# SCH_pump_2021-09-05_easyeda.net
KiCad netlist of a schematic drawn in EasyEDA
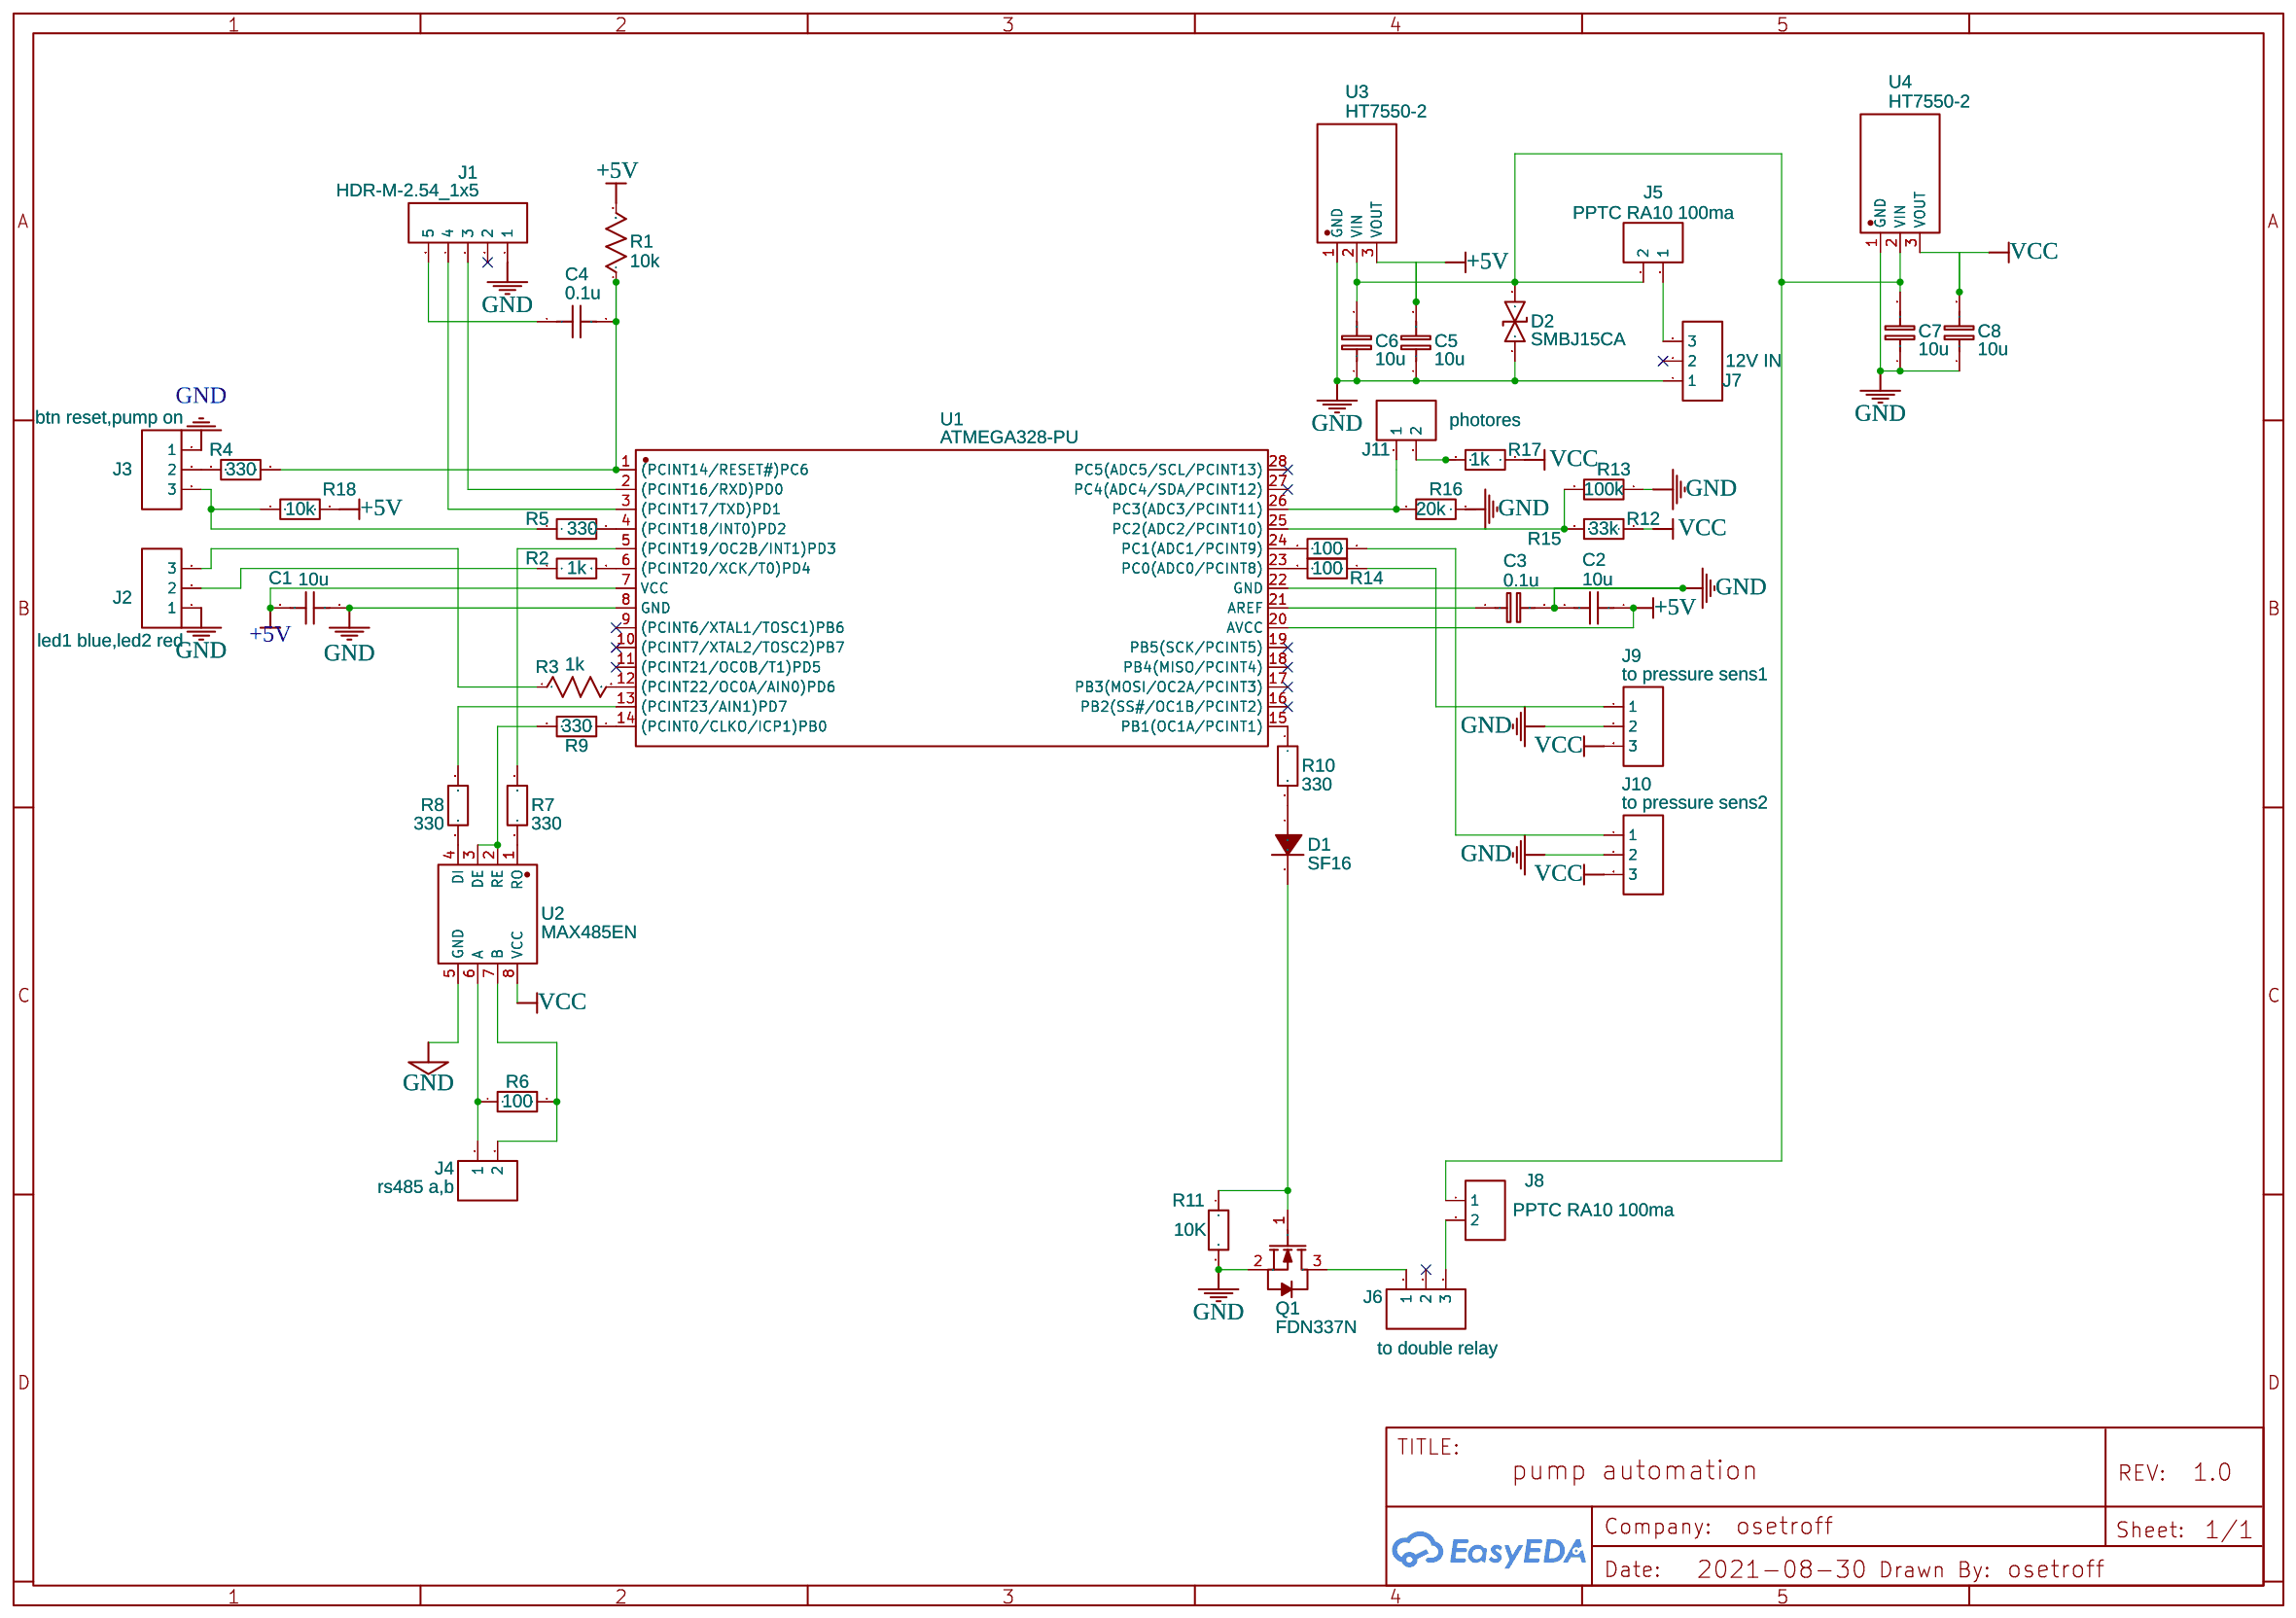
[diagram p0: schematic sheet]

(export (version "E")
  (design (tool "Eeschema 10.0.6"))
  (components
    (comp (ref "C1") (value "10u") (libsource (lib "") (part "C_0603_US")))
    (comp (ref "C2") (value "10u") (libsource (lib "") (part "C_0603_US")))
    (comp (ref "C3") (value "0.1u") (libsource (lib "") (part "C_0603_EU_1")))
    (comp (ref "C4") (value "0.1u") (libsource (lib "") (part "C_0603_US_1")))
    (comp (ref "C5") (value "10u") (libsource (lib "") (part "C_0603_EU")))
    (comp (ref "C6") (value "10u") (libsource (lib "") (part "C_0603_EU")))
    (comp (ref "C7") (value "10u") (libsource (lib "") (part "C_0603_EU")))
    (comp (ref "C8") (value "10u") (libsource (lib "") (part "C_0603_EU")))
    (comp (ref "D1")
      (value "SF16")
      (fields (field (name "BOM_Supplier Part") "C65035"))
      (libsource (lib "") (part "SF16"))
    )
    (comp (ref "D2")
      (value "SMBJ15CA")
      (fields (field (name "BOM_Supplier Part") "C169449"))
      (libsource (lib "") (part "SMBJ15CA"))
    )
    (comp (ref "J1")
      (value "HDR-M-2.54_1x5")
      (fields (field (name "BOM_Supplier Part") "C358687"))
      (libsource (lib "") (part "HDR-M-2.54_1x5"))
    )
    (comp (ref "J2")
      (value "led1 blue,led2 red")
      (fields (field (name "BOM_Supplier Part") "C180248"))
      (libsource (lib "") (part "HDR-M-2.54_1x3_2"))
    )
    (comp (ref "J3")
      (value "btn reset,pump on")
      (fields (field (name "BOM_Supplier Part") "C180248"))
      (libsource (lib "") (part "HDR-M-2.54_1x3_4"))
    )
    (comp (ref "J4")
      (value "rs485 a,b")
      (fields (field (name "BOM_Supplier Part") "C124375"))
      (libsource (lib "") (part "HDR-M-2.54_1x2_2"))
    )
    (comp (ref "J5")
      (value "PPTC RA10 100ma")
      (fields (field (name "BOM_Supplier Part") "C124375"))
      (libsource (lib "") (part "HDR-M-2.54_1x2"))
    )
    (comp (ref "J6")
      (value "to double relay")
      (fields (field (name "BOM_Supplier Part") "C180248"))
      (libsource (lib "") (part "HDR-M-2.54_1x3_3"))
    )
    (comp (ref "J7")
      (value "12V IN")
      (fields (field (name "BOM_Supplier Part") "C180248"))
      (libsource (lib "") (part "HDR-M-2.54_1x3_1"))
    )
    (comp (ref "J8")
      (value "PPTC RA10 100ma")
      (fields (field (name "BOM_Supplier Part") "C124375"))
      (libsource (lib "") (part "HDR-M-2.54_1x2_3"))
    )
    (comp (ref "J9")
      (value "to pressure sens1")
      (fields (field (name "BOM_Supplier Part") "C180248"))
      (libsource (lib "") (part "HDR-M-2.54_1x3"))
    )
    (comp (ref "J10")
      (value "to pressure sens2")
      (fields (field (name "BOM_Supplier Part") "C180248"))
      (libsource (lib "") (part "HDR-M-2.54_1x3"))
    )
    (comp (ref "J11")
      (value "photores")
      (fields (field (name "BOM_Supplier Part") "C124375"))
      (libsource (lib "") (part "HDR-M-2.54_1x2_1"))
    )
    (comp (ref "Q1")
      (value "FDN337N")
      (fields (field (name "BOM_Supplier Part") "C241805"))
      (libsource (lib "") (part "FDN337N"))
    )
    (comp (ref "R1") (value "10k") (libsource (lib "") (part "R_0603_US")))
    (comp (ref "R2") (value "1k") (libsource (lib "") (part "R_0603_EU_1")))
    (comp (ref "R3") (value "1k") (libsource (lib "") (part "R_0603_US_1")))
    (comp (ref "R4") (value "330") (libsource (lib "") (part "R_0603_EU_1")))
    (comp (ref "R5") (value "330") (libsource (lib "") (part "R_0603_EU_1")))
    (comp (ref "R6") (value "100") (libsource (lib "") (part "R_0603_EU_1")))
    (comp (ref "R7") (value "330") (libsource (lib "") (part "R_0603_EU_3")))
    (comp (ref "R8") (value "330") (libsource (lib "") (part "R_0603_EU_2")))
    (comp (ref "R9") (value "330") (libsource (lib "") (part "R_0603_EU")))
    (comp (ref "R10") (value "330") (libsource (lib "") (part "R_0603_EU_2")))
    (comp (ref "R11") (value "10K") (libsource (lib "") (part "R_0603_EU_2")))
    (comp (ref "R12") (value "33k") (libsource (lib "") (part "R_0603_EU")))
    (comp (ref "R13") (value "100k") (libsource (lib "") (part "R_0603_EU")))
    (comp (ref "R14") (value "100") (libsource (lib "") (part "R_0603_EU")))
    (comp (ref "R15") (value "100") (libsource (lib "") (part "R_0603_EU")))
    (comp (ref "R16") (value "20k") (libsource (lib "") (part "R_0603_EU")))
    (comp (ref "R17") (value "1k") (libsource (lib "") (part "R_0603_EU")))
    (comp (ref "R18") (value "10k") (libsource (lib "") (part "R_0603_EU_1")))
    (comp (ref "U1")
      (value "ATMEGA328-PU")
      (fields (field (name "BOM_Supplier Part") "C613508"))
      (libsource (lib "") (part "ATMEGA328-PU"))
    )
    (comp (ref "U2")
      (value "MAX485EN")
      (fields (field (name "BOM_Supplier Part") "C481665"))
      (libsource (lib "") (part "MAX485EN"))
    )
    (comp (ref "U3")
      (value "HT7550-2")
      (fields (field (name "BOM_Supplier Part") "C131464"))
      (libsource (lib "") (part "HT7550-2"))
    )
    (comp (ref "U4")
      (value "HT7550-2")
      (fields (field (name "BOM_Supplier Part") "C131464"))
      (libsource (lib "") (part "HT7550-2"))
    )
  )
  (nets
    (net (code "1") (name "+5V") (class "Default")
      (node (ref "C1") (pin "2") (pinfunction "2_2") (pintype "unspecified"))
      (node (ref "C2") (pin "1") (pinfunction "1_1") (pintype "unspecified"))
      (node (ref "C5") (pin "2") (pinfunction "2_2") (pintype "unspecified"))
      (node (ref "R1") (pin "2") (pinfunction "2_2") (pintype "unspecified"))
      (node (ref "R18") (pin "2") (pinfunction "2_2") (pintype "unspecified"))
      (node (ref "U1") (pin "20") (pinfunction "AVCC_20") (pintype "unspecified"))
      (node (ref "U1") (pin "7") (pinfunction "VCC_7") (pintype "unspecified"))
      (node (ref "U3") (pin "3") (pinfunction "VOUT_3") (pintype "unspecified"))
    )
    (net (code "2") (name "GND") (class "Default")
      (node (ref "C1") (pin "1") (pinfunction "1_1") (pintype "unspecified"))
      (node (ref "C2") (pin "2") (pinfunction "2_2") (pintype "unspecified"))
      (node (ref "C3") (pin "2") (pinfunction "2_2") (pintype "unspecified"))
      (node (ref "C5") (pin "1") (pinfunction "1_1") (pintype "unspecified"))
      (node (ref "C6") (pin "1") (pinfunction "1_1") (pintype "unspecified"))
      (node (ref "C7") (pin "1") (pinfunction "1_1") (pintype "unspecified"))
      (node (ref "C8") (pin "1") (pinfunction "1_1") (pintype "unspecified"))
      (node (ref "D2") (pin "1") (pinfunction "1_1") (pintype "unspecified"))
      (node (ref "J1") (pin "1") (pinfunction "1_1") (pintype "unspecified"))
      (node (ref "J10") (pin "2") (pinfunction "2_2") (pintype "input"))
      (node (ref "J2") (pin "1") (pinfunction "1_1") (pintype "input"))
      (node (ref "J3") (pin "1") (pinfunction "1_1") (pintype "input"))
      (node (ref "J7") (pin "1") (pinfunction "1_1") (pintype "input"))
      (node (ref "J9") (pin "2") (pinfunction "2_2") (pintype "input"))
      (node (ref "Q1") (pin "2") (pinfunction "S_2") (pintype "unspecified"))
      (node (ref "R11") (pin "2") (pinfunction "2_2") (pintype "unspecified"))
      (node (ref "R13") (pin "1") (pinfunction "1_1") (pintype "unspecified"))
      (node (ref "R16") (pin "1") (pinfunction "1_1") (pintype "unspecified"))
      (node (ref "U1") (pin "22") (pinfunction "GND_22") (pintype "unspecified"))
      (node (ref "U1") (pin "8") (pinfunction "GND_8") (pintype "unspecified"))
      (node (ref "U2") (pin "5") (pinfunction "GND_5") (pintype "unspecified"))
      (node (ref "U3") (pin "1") (pinfunction "GND_1") (pintype "unspecified"))
      (node (ref "U4") (pin "1") (pinfunction "GND_1") (pintype "unspecified"))
    )
    (net (code "3") (name "Net-(C4-Pad1)") (class "Default")
      (node (ref "C4") (pin "1") (pinfunction "1_1") (pintype "unspecified"))
      (node (ref "J1") (pin "5") (pinfunction "5_5") (pintype "unspecified"))
    )
    (net (code "4") (name "Net-(D1-A)") (class "Default")
      (node (ref "D1") (pin "1") (pinfunction "A_1") (pintype "unspecified"))
      (node (ref "R10") (pin "2") (pinfunction "2_2") (pintype "unspecified"))
    )
    (net (code "5") (name "Net-(D1-C)") (class "Default")
      (node (ref "D1") (pin "2") (pinfunction "C_2") (pintype "unspecified"))
      (node (ref "Q1") (pin "1") (pinfunction "G_1") (pintype "unspecified"))
      (node (ref "R11") (pin "1") (pinfunction "1_1") (pintype "unspecified"))
    )
    (net (code "6") (name "Net-(J2-Pad2)") (class "Default")
      (node (ref "J2") (pin "2") (pinfunction "2_2") (pintype "input"))
      (node (ref "R2") (pin "1") (pinfunction "1_1") (pintype "unspecified"))
    )
    (net (code "7") (name "Net-(J2-Pad3)") (class "Default")
      (node (ref "J2") (pin "3") (pinfunction "3_3") (pintype "input"))
      (node (ref "R3") (pin "1") (pinfunction "1_1") (pintype "unspecified"))
    )
    (net (code "8") (name "Net-(J3-Pad2)") (class "Default")
      (node (ref "J3") (pin "2") (pinfunction "2_2") (pintype "input"))
      (node (ref "R4") (pin "1") (pinfunction "1_1") (pintype "unspecified"))
    )
    (net (code "9") (name "Net-(J3-Pad3)") (class "Default")
      (node (ref "J3") (pin "3") (pinfunction "3_3") (pintype "input"))
      (node (ref "R18") (pin "1") (pinfunction "1_1") (pintype "unspecified"))
      (node (ref "R5") (pin "1") (pinfunction "1_1") (pintype "unspecified"))
    )
    (net (code "10") (name "Net-(J5-Pad1)") (class "Default")
      (node (ref "J5") (pin "1") (pinfunction "1_1") (pintype "unspecified"))
      (node (ref "J7") (pin "3") (pinfunction "3_3") (pintype "input"))
    )
    (net (code "11") (name "Net-(J6-Pad3)") (class "Default")
      (node (ref "J6") (pin "3") (pinfunction "3_3") (pintype "input"))
      (node (ref "J8") (pin "2") (pinfunction "2_2") (pintype "unspecified"))
    )
    (net (code "12") (name "Net-(J9-Pad1)") (class "Default")
      (node (ref "J9") (pin "1") (pinfunction "1_1") (pintype "input"))
      (node (ref "R14") (pin "1") (pinfunction "1_1") (pintype "unspecified"))
    )
    (net (code "13") (name "Net-(J10-Pad1)") (class "Default")
      (node (ref "J10") (pin "1") (pinfunction "1_1") (pintype "input"))
      (node (ref "R15") (pin "1") (pinfunction "1_1") (pintype "unspecified"))
    )
    (net (code "14") (name "Net-(J11-Pad2)") (class "Default")
      (node (ref "J11") (pin "2") (pinfunction "2_2") (pintype "unspecified"))
      (node (ref "R17") (pin "2") (pinfunction "2_2") (pintype "unspecified"))
    )
    (net (code "15") (name "Net-(Q1-D)") (class "Default")
      (node (ref "J6") (pin "1") (pinfunction "1_1") (pintype "input"))
      (node (ref "Q1") (pin "3") (pinfunction "D_3") (pintype "unspecified"))
    )
    (net (code "16") (name "Net-(U1-(PCINT0{slash}CLKO{slash}ICP1)PB0)") (class "Default")
      (node (ref "R9") (pin "1") (pinfunction "1_1") (pintype "unspecified"))
      (node (ref "U1") (pin "14") (pinfunction "(PCINT0/CLKO/ICP1)PB0_14") (pintype "unspecified"))
    )
    (net (code "17") (name "Net-(U1-(PCINT14{slash}RESET#)PC6)") (class "Default")
      (node (ref "C4") (pin "2") (pinfunction "2_2") (pintype "unspecified"))
      (node (ref "R1") (pin "1") (pinfunction "1_1") (pintype "unspecified"))
      (node (ref "R4") (pin "2") (pinfunction "2_2") (pintype "unspecified"))
      (node (ref "U1") (pin "1") (pinfunction "(PCINT14/RESET#)PC6_1") (pintype "unspecified"))
    )
    (net (code "18") (name "Net-(U1-(PCINT16{slash}RXD)PD0)") (class "Default")
      (node (ref "J1") (pin "3") (pinfunction "3_3") (pintype "unspecified"))
      (node (ref "U1") (pin "2") (pinfunction "(PCINT16/RXD)PD0_2") (pintype "unspecified"))
    )
    (net (code "19") (name "Net-(U1-(PCINT17{slash}TXD)PD1)") (class "Default")
      (node (ref "J1") (pin "4") (pinfunction "4_4") (pintype "unspecified"))
      (node (ref "U1") (pin "3") (pinfunction "(PCINT17/TXD)PD1_3") (pintype "unspecified"))
    )
    (net (code "20") (name "Net-(U1-(PCINT18{slash}INT0)PD2)") (class "Default")
      (node (ref "R5") (pin "2") (pinfunction "2_2") (pintype "unspecified"))
      (node (ref "U1") (pin "4") (pinfunction "(PCINT18/INT0)PD2_4") (pintype "unspecified"))
    )
    (net (code "21") (name "Net-(U1-(PCINT19{slash}OC2B{slash}INT1)PD3)") (class "Default")
      (node (ref "R7") (pin "2") (pinfunction "2_2") (pintype "unspecified"))
      (node (ref "U1") (pin "5") (pinfunction "(PCINT19/OC2B/INT1)PD3_5") (pintype "unspecified"))
    )
    (net (code "22") (name "Net-(U1-(PCINT20{slash}XCK{slash}T0)PD4)") (class "Default")
      (node (ref "R2") (pin "2") (pinfunction "2_2") (pintype "unspecified"))
      (node (ref "U1") (pin "6") (pinfunction "(PCINT20/XCK/T0)PD4_6") (pintype "unspecified"))
    )
    (net (code "23") (name "Net-(U1-(PCINT22{slash}OC0A{slash}AIN0)PD6)") (class "Default")
      (node (ref "R3") (pin "2") (pinfunction "2_2") (pintype "unspecified"))
      (node (ref "U1") (pin "12") (pinfunction "(PCINT22/OC0A/AIN0)PD6_12") (pintype "unspecified"))
    )
    (net (code "24") (name "Net-(U1-(PCINT23{slash}AIN1)PD7)") (class "Default")
      (node (ref "R8") (pin "1") (pinfunction "1_1") (pintype "unspecified"))
      (node (ref "U1") (pin "13") (pinfunction "(PCINT23/AIN1)PD7_13") (pintype "unspecified"))
    )
    (net (code "25") (name "Net-(U1-AREF)") (class "Default")
      (node (ref "C3") (pin "1") (pinfunction "1_1") (pintype "unspecified"))
      (node (ref "U1") (pin "21") (pinfunction "AREF_21") (pintype "unspecified"))
    )
    (net (code "26") (name "Net-(U1-PB1(OC1A{slash}PCINT1))") (class "Default")
      (node (ref "R10") (pin "1") (pinfunction "1_1") (pintype "unspecified"))
      (node (ref "U1") (pin "15") (pinfunction "PB1(OC1A/PCINT1)_15") (pintype "unspecified"))
    )
    (net (code "27") (name "Net-(U1-PC0(ADC0{slash}PCINT8))") (class "Default")
      (node (ref "R14") (pin "2") (pinfunction "2_2") (pintype "unspecified"))
      (node (ref "U1") (pin "23") (pinfunction "PC0(ADC0/PCINT8)_23") (pintype "unspecified"))
    )
    (net (code "28") (name "Net-(U1-PC1(ADC1{slash}PCINT9))") (class "Default")
      (node (ref "R15") (pin "2") (pinfunction "2_2") (pintype "unspecified"))
      (node (ref "U1") (pin "24") (pinfunction "PC1(ADC1/PCINT9)_24") (pintype "unspecified"))
    )
    (net (code "29") (name "Net-(U1-PC2(ADC2{slash}PCINT10))") (class "Default")
      (node (ref "R12") (pin "2") (pinfunction "2_2") (pintype "unspecified"))
      (node (ref "R13") (pin "2") (pinfunction "2_2") (pintype "unspecified"))
      (node (ref "U1") (pin "25") (pinfunction "PC2(ADC2/PCINT10)_25") (pintype "unspecified"))
    )
    (net (code "30") (name "Net-(U1-PC3(ADC3{slash}PCINT11))") (class "Default")
      (node (ref "J11") (pin "1") (pinfunction "1_1") (pintype "unspecified"))
      (node (ref "R16") (pin "2") (pinfunction "2_2") (pintype "unspecified"))
      (node (ref "U1") (pin "26") (pinfunction "PC3(ADC3/PCINT11)_26") (pintype "unspecified"))
    )
    (net (code "31") (name "Net-(U2-A)") (class "Default")
      (node (ref "J4") (pin "1") (pinfunction "1_1") (pintype "unspecified"))
      (node (ref "R6") (pin "1") (pinfunction "1_1") (pintype "unspecified"))
      (node (ref "U2") (pin "6") (pinfunction "A_6") (pintype "unspecified"))
    )
    (net (code "32") (name "Net-(U2-B)") (class "Default")
      (node (ref "J4") (pin "2") (pinfunction "2_2") (pintype "unspecified"))
      (node (ref "R6") (pin "2") (pinfunction "2_2") (pintype "unspecified"))
      (node (ref "U2") (pin "7") (pinfunction "B_7") (pintype "unspecified"))
    )
    (net (code "33") (name "Net-(U2-DE)") (class "Default")
      (node (ref "R9") (pin "2") (pinfunction "2_2") (pintype "unspecified"))
      (node (ref "U2") (pin "2") (pinfunction "RE_2") (pintype "unspecified"))
      (node (ref "U2") (pin "3") (pinfunction "DE_3") (pintype "unspecified"))
    )
    (net (code "34") (name "Net-(U2-DI)") (class "Default")
      (node (ref "R8") (pin "2") (pinfunction "2_2") (pintype "unspecified"))
      (node (ref "U2") (pin "4") (pinfunction "DI_4") (pintype "unspecified"))
    )
    (net (code "35") (name "Net-(U2-RO)") (class "Default")
      (node (ref "R7") (pin "1") (pinfunction "1_1") (pintype "unspecified"))
      (node (ref "U2") (pin "1") (pinfunction "RO_1") (pintype "unspecified"))
    )
    (net (code "36") (name "Net-(U3-VIN)") (class "Default")
      (node (ref "C6") (pin "2") (pinfunction "2_2") (pintype "unspecified"))
      (node (ref "C7") (pin "2") (pinfunction "2_2") (pintype "unspecified"))
      (node (ref "D2") (pin "2") (pinfunction "2_2") (pintype "unspecified"))
      (node (ref "J5") (pin "2") (pinfunction "2_2") (pintype "unspecified"))
      (node (ref "J8") (pin "1") (pinfunction "1_1") (pintype "unspecified"))
      (node (ref "U3") (pin "2") (pinfunction "VIN_2") (pintype "unspecified"))
      (node (ref "U4") (pin "2") (pinfunction "VIN_2") (pintype "unspecified"))
    )
    (net (code "37") (name "VCC") (class "Default")
      (node (ref "C8") (pin "2") (pinfunction "2_2") (pintype "unspecified"))
      (node (ref "J10") (pin "3") (pinfunction "3_3") (pintype "input"))
      (node (ref "J9") (pin "3") (pinfunction "3_3") (pintype "input"))
      (node (ref "R12") (pin "1") (pinfunction "1_1") (pintype "unspecified"))
      (node (ref "R17") (pin "1") (pinfunction "1_1") (pintype "unspecified"))
      (node (ref "U2") (pin "8") (pinfunction "VCC_8") (pintype "unspecified"))
      (node (ref "U4") (pin "3") (pinfunction "VOUT_3") (pintype "unspecified"))
    )
    (net (code "38") (name "unconnected-(J1-Pad2)") (class "Default")
      (node (ref "J1") (pin "2") (pinfunction "2_2") (pintype "unspecified+no_connect"))
    )
    (net (code "39") (name "unconnected-(J6-Pad2)") (class "Default")
      (node (ref "J6") (pin "2") (pinfunction "2_2") (pintype "input+no_connect"))
    )
    (net (code "40") (name "unconnected-(J7-Pad2)") (class "Default")
      (node (ref "J7") (pin "2") (pinfunction "2_2") (pintype "input+no_connect"))
    )
    (net (code "41") (name "unconnected-(U1-(PCINT6{slash}XTAL1{slash}TOSC1)PB6-Pad9)") (class "Default")
      (node (ref "U1") (pin "9") (pinfunction "(PCINT6/XTAL1/TOSC1)PB6_9") (pintype "unspecified+no_connect"))
    )
    (net (code "42") (name "unconnected-(U1-(PCINT7{slash}XTAL2{slash}TOSC2)PB7-Pad10)") (class "Default")
      (node (ref "U1") (pin "10") (pinfunction "(PCINT7/XTAL2/TOSC2)PB7_10") (pintype "unspecified+no_connect"))
    )
    (net (code "43") (name "unconnected-(U1-(PCINT21{slash}OC0B{slash}T1)PD5-Pad11)") (class "Default")
      (node (ref "U1") (pin "11") (pinfunction "(PCINT21/OC0B/T1)PD5_11") (pintype "unspecified+no_connect"))
    )
    (net (code "44") (name "unconnected-(U1-PB2(SS#{slash}OC1B{slash}PCINT2)-Pad16)") (class "Default")
      (node (ref "U1") (pin "16") (pinfunction "PB2(SS#/OC1B/PCINT2)_16") (pintype "unspecified+no_connect"))
    )
    (net (code "45") (name "unconnected-(U1-PB3(MOSI{slash}OC2A{slash}PCINT3)-Pad17)") (class "Default")
      (node (ref "U1") (pin "17") (pinfunction "PB3(MOSI/OC2A/PCINT3)_17") (pintype "unspecified+no_connect"))
    )
    (net (code "46") (name "unconnected-(U1-PB4(MISO{slash}PCINT4)-Pad18)") (class "Default")
      (node (ref "U1") (pin "18") (pinfunction "PB4(MISO/PCINT4)_18") (pintype "unspecified+no_connect"))
    )
    (net (code "47") (name "unconnected-(U1-PB5(SCK{slash}PCINT5)-Pad19)") (class "Default")
      (node (ref "U1") (pin "19") (pinfunction "PB5(SCK/PCINT5)_19") (pintype "unspecified+no_connect"))
    )
    (net (code "48") (name "unconnected-(U1-PC4(ADC4{slash}SDA{slash}PCINT12)-Pad27)") (class "Default")
      (node (ref "U1") (pin "27") (pinfunction "PC4(ADC4/SDA/PCINT12)_27") (pintype "unspecified+no_connect"))
    )
    (net (code "49") (name "unconnected-(U1-PC5(ADC5{slash}SCL{slash}PCINT13)-Pad28)") (class "Default")
      (node (ref "U1") (pin "28") (pinfunction "PC5(ADC5/SCL/PCINT13)_28") (pintype "unspecified+no_connect"))
    )
  )
)
